# a323-vcf.net
KiCad netlist of a schematic drawn in EAGLE
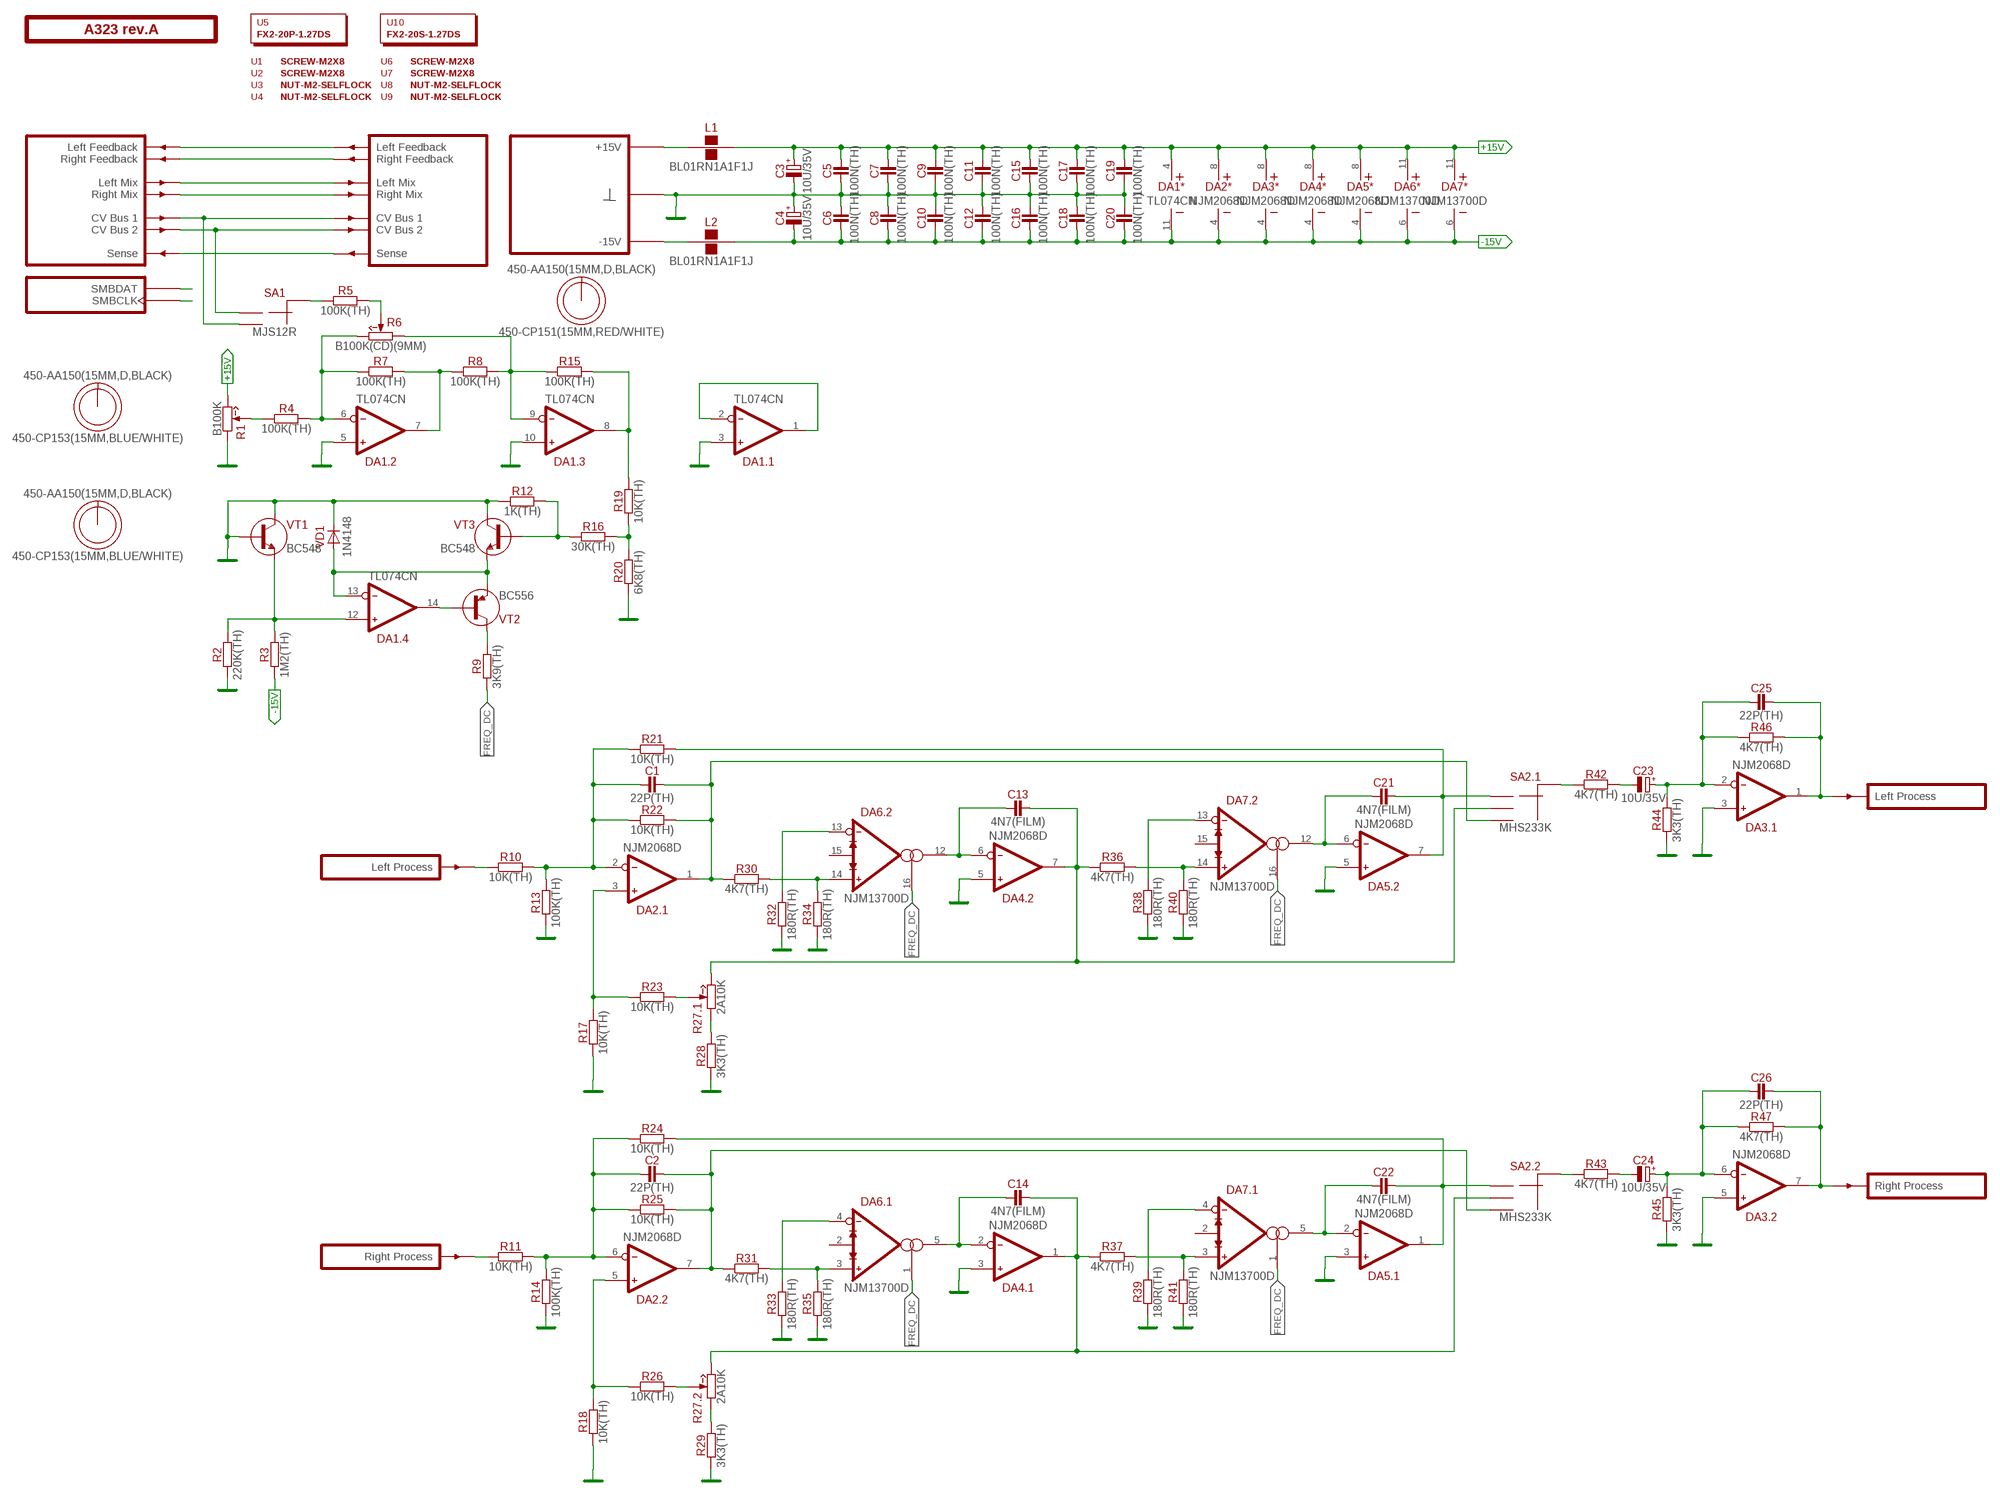
[diagram p0: schematic, sheet 1]

(export (version "E")
  (design (tool "Eeschema 10.0.6"))
  (components
    (comp (ref "C1")
      (value "22P(TH)")
      (footprint "eagle-import:C050-024X044")
      (libsource (lib "eagle-import") (part "?22P(TH)"))
    )
    (comp (ref "C2")
      (value "22P(TH)")
      (footprint "eagle-import:C050-024X044")
      (libsource (lib "eagle-import") (part "?22P(TH)"))
    )
    (comp (ref "C3")
      (value "10U/35V")
      (footprint "eagle-import:E2-5")
      (libsource (lib "eagle-import") (part "?10U/35V"))
    )
    (comp (ref "C4")
      (value "10U/35V")
      (footprint "eagle-import:E2-5")
      (libsource (lib "eagle-import") (part "?10U/35V"))
    )
    (comp (ref "C5")
      (value "100N(TH)")
      (footprint "eagle-import:C050-024X044")
      (libsource (lib "eagle-import") (part "?100N(TH)"))
    )
    (comp (ref "C6")
      (value "100N(TH)")
      (footprint "eagle-import:C050-024X044")
      (libsource (lib "eagle-import") (part "?100N(TH)"))
    )
    (comp (ref "C7")
      (value "100N(TH)")
      (footprint "eagle-import:C050-024X044")
      (libsource (lib "eagle-import") (part "?100N(TH)"))
    )
    (comp (ref "C8")
      (value "100N(TH)")
      (footprint "eagle-import:C050-024X044")
      (libsource (lib "eagle-import") (part "?100N(TH)"))
    )
    (comp (ref "C9")
      (value "100N(TH)")
      (footprint "eagle-import:C050-024X044")
      (libsource (lib "eagle-import") (part "?100N(TH)"))
    )
    (comp (ref "C10")
      (value "100N(TH)")
      (footprint "eagle-import:C050-024X044")
      (libsource (lib "eagle-import") (part "?100N(TH)"))
    )
    (comp (ref "C11")
      (value "100N(TH)")
      (footprint "eagle-import:C050-024X044")
      (libsource (lib "eagle-import") (part "?100N(TH)"))
    )
    (comp (ref "C12")
      (value "100N(TH)")
      (footprint "eagle-import:C050-024X044")
      (libsource (lib "eagle-import") (part "?100N(TH)"))
    )
    (comp (ref "C13")
      (value "4N7(FILM)")
      (footprint "eagle-import:C050-025X075")
      (libsource (lib "eagle-import") (part "?4N7(FILM)"))
    )
    (comp (ref "C14")
      (value "4N7(FILM)")
      (footprint "eagle-import:C050-025X075")
      (libsource (lib "eagle-import") (part "?4N7(FILM)"))
    )
    (comp (ref "C15")
      (value "100N(TH)")
      (footprint "eagle-import:C050-024X044")
      (libsource (lib "eagle-import") (part "?100N(TH)"))
    )
    (comp (ref "C16")
      (value "100N(TH)")
      (footprint "eagle-import:C050-024X044")
      (libsource (lib "eagle-import") (part "?100N(TH)"))
    )
    (comp (ref "C17")
      (value "100N(TH)")
      (footprint "eagle-import:C050-024X044")
      (libsource (lib "eagle-import") (part "?100N(TH)"))
    )
    (comp (ref "C18")
      (value "100N(TH)")
      (footprint "eagle-import:C050-024X044")
      (libsource (lib "eagle-import") (part "?100N(TH)"))
    )
    (comp (ref "C19")
      (value "100N(TH)")
      (footprint "eagle-import:C050-024X044")
      (libsource (lib "eagle-import") (part "?100N(TH)"))
    )
    (comp (ref "C20")
      (value "100N(TH)")
      (footprint "eagle-import:C050-024X044")
      (libsource (lib "eagle-import") (part "?100N(TH)"))
    )
    (comp (ref "C21")
      (value "4N7(FILM)")
      (footprint "eagle-import:C050-025X075")
      (libsource (lib "eagle-import") (part "?4N7(FILM)"))
    )
    (comp (ref "C22")
      (value "4N7(FILM)")
      (footprint "eagle-import:C050-025X075")
      (libsource (lib "eagle-import") (part "?4N7(FILM)"))
    )
    (comp (ref "C23")
      (value "10U/35V")
      (footprint "eagle-import:E2-5")
      (libsource (lib "eagle-import") (part "?10U/35V"))
    )
    (comp (ref "C24")
      (value "10U/35V")
      (footprint "eagle-import:E2-5")
      (libsource (lib "eagle-import") (part "?10U/35V"))
    )
    (comp (ref "C25")
      (value "22P(TH)")
      (footprint "eagle-import:C050-024X044")
      (libsource (lib "eagle-import") (part "?22P(TH)"))
    )
    (comp (ref "C26")
      (value "22P(TH)")
      (footprint "eagle-import:C050-024X044")
      (libsource (lib "eagle-import") (part "?22P(TH)"))
    )
    (comp (ref "DA1")
      (value "TL074CN")
      (footprint "eagle-import:DIP-14")
      (libsource (lib "eagle-import") (part "TL074CN"))
    )
    (comp (ref "DA2")
      (value "NJM2068D")
      (footprint "eagle-import:DIP-8")
      (libsource (lib "eagle-import") (part "NJM2068D"))
    )
    (comp (ref "DA3")
      (value "NJM2068D")
      (footprint "eagle-import:DIP-8")
      (libsource (lib "eagle-import") (part "NJM2068D"))
    )
    (comp (ref "DA4")
      (value "NJM2068D")
      (footprint "eagle-import:DIP-8")
      (libsource (lib "eagle-import") (part "NJM2068D"))
    )
    (comp (ref "DA5")
      (value "NJM2068D")
      (footprint "eagle-import:DIP-8")
      (libsource (lib "eagle-import") (part "NJM2068D"))
    )
    (comp (ref "DA6")
      (value "NJM13700D")
      (footprint "eagle-import:DIP-16")
      (libsource (lib "eagle-import") (part "NJM13700D"))
    )
    (comp (ref "DA7")
      (value "NJM13700D")
      (footprint "eagle-import:DIP-16")
      (libsource (lib "eagle-import") (part "NJM13700D"))
    )
    (comp (ref "L1")
      (value "BL01RN1A1F1J")
      (footprint "eagle-import:BL01RN1A")
      (libsource (lib "eagle-import") (part "BL01RN1A?1F1J"))
    )
    (comp (ref "L2")
      (value "BL01RN1A1F1J")
      (footprint "eagle-import:BL01RN1A")
      (libsource (lib "eagle-import") (part "BL01RN1A?1F1J"))
    )
    (comp (ref "O1")
      (value "450-AA150(15MM,D,BLACK)")
      (footprint "eagle-import:EMPTY")
      (libsource (lib "eagle-import") (part "450-AA?150(15MM,D,BLACK)"))
    )
    (comp (ref "O2")
      (value "450-CP153(15MM,BLUE/WHITE)")
      (footprint "eagle-import:EMPTY")
      (libsource (lib "eagle-import") (part "450-C?P153(15MM,BLUE/WHITE)"))
    )
    (comp (ref "O3")
      (value "450-AA150(15MM,D,BLACK)")
      (footprint "eagle-import:EMPTY")
      (libsource (lib "eagle-import") (part "450-AA?150(15MM,D,BLACK)"))
    )
    (comp (ref "O4")
      (value "450-CP153(15MM,BLUE/WHITE)")
      (footprint "eagle-import:EMPTY")
      (libsource (lib "eagle-import") (part "450-C?P153(15MM,BLUE/WHITE)"))
    )
    (comp (ref "O5")
      (value "450-AA150(15MM,D,BLACK)")
      (footprint "eagle-import:EMPTY")
      (libsource (lib "eagle-import") (part "450-AA?150(15MM,D,BLACK)"))
    )
    (comp (ref "O6")
      (value "450-CP151(15MM,RED/WHITE)")
      (footprint "eagle-import:EMPTY")
      (libsource (lib "eagle-import") (part "450-C?P151(15MM,RED/WHITE)"))
    )
    (comp (ref "PCB1")
      (value "A323 rev.A")
      (footprint "eagle-import:ST2-BOARD-74")
      (libsource (lib "eagle-import") (part "ST2-BOARD-?74"))
    )
    (comp (ref "R1")
      (value "B100K")
      (footprint "eagle-import:RV11-SINGLE")
      (libsource (lib "eagle-import") (part "?B100K"))
    )
    (comp (ref "R2")
      (value "220K(TH)")
      (footprint "eagle-import:R-0207_10")
      (libsource (lib "eagle-import") (part "?220K(TH)"))
    )
    (comp (ref "R3")
      (value "1M2(TH)")
      (footprint "eagle-import:R-0207_10")
      (libsource (lib "eagle-import") (part "?1M2(TH)"))
    )
    (comp (ref "R4")
      (value "100K(TH)")
      (footprint "eagle-import:R-0207_10")
      (libsource (lib "eagle-import") (part "?100K(TH)"))
    )
    (comp (ref "R5")
      (value "100K(TH)")
      (footprint "eagle-import:R-0207_10")
      (libsource (lib "eagle-import") (part "?100K(TH)"))
    )
    (comp (ref "R6")
      (value "B100K(CD)(9MM)")
      (footprint "eagle-import:RV09-SINGLE")
      (libsource (lib "eagle-import") (part "?B100K(CD)(9MM)"))
    )
    (comp (ref "R7")
      (value "100K(TH)")
      (footprint "eagle-import:R-0207_10")
      (libsource (lib "eagle-import") (part "?100K(TH)"))
    )
    (comp (ref "R8")
      (value "100K(TH)")
      (footprint "eagle-import:R-0207_10")
      (libsource (lib "eagle-import") (part "?100K(TH)"))
    )
    (comp (ref "R9")
      (value "3K9(TH)")
      (footprint "eagle-import:R-0207_10")
      (libsource (lib "eagle-import") (part "?3K9(TH)"))
    )
    (comp (ref "R10")
      (value "10K(TH)")
      (footprint "eagle-import:R-0207_10")
      (libsource (lib "eagle-import") (part "?10K(TH)"))
    )
    (comp (ref "R11")
      (value "10K(TH)")
      (footprint "eagle-import:R-0207_10")
      (libsource (lib "eagle-import") (part "?10K(TH)"))
    )
    (comp (ref "R12")
      (value "1K(TH)")
      (footprint "eagle-import:R-0207_10")
      (libsource (lib "eagle-import") (part "?1K(TH)"))
    )
    (comp (ref "R13")
      (value "100K(TH)")
      (footprint "eagle-import:R-0207_10")
      (libsource (lib "eagle-import") (part "?100K(TH)"))
    )
    (comp (ref "R14")
      (value "100K(TH)")
      (footprint "eagle-import:R-0207_10")
      (libsource (lib "eagle-import") (part "?100K(TH)"))
    )
    (comp (ref "R15")
      (value "100K(TH)")
      (footprint "eagle-import:R-0207_10")
      (libsource (lib "eagle-import") (part "?100K(TH)"))
    )
    (comp (ref "R16")
      (value "30K(TH)")
      (footprint "eagle-import:R-0207_10")
      (libsource (lib "eagle-import") (part "?30K(TH)"))
    )
    (comp (ref "R17")
      (value "10K(TH)")
      (footprint "eagle-import:R-0207_10")
      (libsource (lib "eagle-import") (part "?10K(TH)"))
    )
    (comp (ref "R18")
      (value "10K(TH)")
      (footprint "eagle-import:R-0207_10")
      (libsource (lib "eagle-import") (part "?10K(TH)"))
    )
    (comp (ref "R19")
      (value "10K(TH)")
      (footprint "eagle-import:R-0207_10")
      (libsource (lib "eagle-import") (part "?10K(TH)"))
    )
    (comp (ref "R20")
      (value "6K8(TH)")
      (footprint "eagle-import:R-0207_10")
      (libsource (lib "eagle-import") (part "?6K8(TH)"))
    )
    (comp (ref "R21")
      (value "10K(TH)")
      (footprint "eagle-import:R-0207_10")
      (libsource (lib "eagle-import") (part "?10K(TH)"))
    )
    (comp (ref "R22")
      (value "10K(TH)")
      (footprint "eagle-import:R-0207_10")
      (libsource (lib "eagle-import") (part "?10K(TH)"))
    )
    (comp (ref "R23")
      (value "10K(TH)")
      (footprint "eagle-import:R-0207_10")
      (libsource (lib "eagle-import") (part "?10K(TH)"))
    )
    (comp (ref "R24")
      (value "10K(TH)")
      (footprint "eagle-import:R-0207_10")
      (libsource (lib "eagle-import") (part "?10K(TH)"))
    )
    (comp (ref "R25")
      (value "10K(TH)")
      (footprint "eagle-import:R-0207_10")
      (libsource (lib "eagle-import") (part "?10K(TH)"))
    )
    (comp (ref "R26")
      (value "10K(TH)")
      (footprint "eagle-import:R-0207_10")
      (libsource (lib "eagle-import") (part "?10K(TH)"))
    )
    (comp (ref "R27")
      (value "2A10K")
      (footprint "eagle-import:RV11-DUAL")
      (libsource (lib "eagle-import") (part "2?A10K"))
    )
    (comp (ref "R28")
      (value "3K3(TH)")
      (footprint "eagle-import:R-0207_10")
      (libsource (lib "eagle-import") (part "?3K3(TH)"))
    )
    (comp (ref "R29")
      (value "3K3(TH)")
      (footprint "eagle-import:R-0207_10")
      (libsource (lib "eagle-import") (part "?3K3(TH)"))
    )
    (comp (ref "R30")
      (value "4K7(TH)")
      (footprint "eagle-import:R-0207_10")
      (libsource (lib "eagle-import") (part "?4K7(TH)"))
    )
    (comp (ref "R31")
      (value "4K7(TH)")
      (footprint "eagle-import:R-0207_10")
      (libsource (lib "eagle-import") (part "?4K7(TH)"))
    )
    (comp (ref "R32")
      (value "180R(TH)")
      (footprint "eagle-import:R-0207_10")
      (libsource (lib "eagle-import") (part "?180R(TH)"))
    )
    (comp (ref "R33")
      (value "180R(TH)")
      (footprint "eagle-import:R-0207_10")
      (libsource (lib "eagle-import") (part "?180R(TH)"))
    )
    (comp (ref "R34")
      (value "180R(TH)")
      (footprint "eagle-import:R-0207_10")
      (libsource (lib "eagle-import") (part "?180R(TH)"))
    )
    (comp (ref "R35")
      (value "180R(TH)")
      (footprint "eagle-import:R-0207_10")
      (libsource (lib "eagle-import") (part "?180R(TH)"))
    )
    (comp (ref "R36")
      (value "4K7(TH)")
      (footprint "eagle-import:R-0207_10")
      (libsource (lib "eagle-import") (part "?4K7(TH)"))
    )
    (comp (ref "R37")
      (value "4K7(TH)")
      (footprint "eagle-import:R-0207_10")
      (libsource (lib "eagle-import") (part "?4K7(TH)"))
    )
    (comp (ref "R38")
      (value "180R(TH)")
      (footprint "eagle-import:R-0207_10")
      (libsource (lib "eagle-import") (part "?180R(TH)"))
    )
    (comp (ref "R39")
      (value "180R(TH)")
      (footprint "eagle-import:R-0207_10")
      (libsource (lib "eagle-import") (part "?180R(TH)"))
    )
    (comp (ref "R40")
      (value "180R(TH)")
      (footprint "eagle-import:R-0207_10")
      (libsource (lib "eagle-import") (part "?180R(TH)"))
    )
    (comp (ref "R41")
      (value "180R(TH)")
      (footprint "eagle-import:R-0207_10")
      (libsource (lib "eagle-import") (part "?180R(TH)"))
    )
    (comp (ref "R42")
      (value "4K7(TH)")
      (footprint "eagle-import:R-0207_10")
      (libsource (lib "eagle-import") (part "?4K7(TH)"))
    )
    (comp (ref "R43")
      (value "4K7(TH)")
      (footprint "eagle-import:R-0207_10")
      (libsource (lib "eagle-import") (part "?4K7(TH)"))
    )
    (comp (ref "R44")
      (value "3K3(TH)")
      (footprint "eagle-import:R-0207_10")
      (libsource (lib "eagle-import") (part "?3K3(TH)"))
    )
    (comp (ref "R45")
      (value "3K3(TH)")
      (footprint "eagle-import:R-0207_10")
      (libsource (lib "eagle-import") (part "?3K3(TH)"))
    )
    (comp (ref "R46")
      (value "4K7(TH)")
      (footprint "eagle-import:R-0207_10")
      (libsource (lib "eagle-import") (part "?4K7(TH)"))
    )
    (comp (ref "R47")
      (value "4K7(TH)")
      (footprint "eagle-import:R-0207_10")
      (libsource (lib "eagle-import") (part "?4K7(TH)"))
    )
    (comp (ref "SA1")
      (value "MJS12R")
      (footprint "eagle-import:APEM-MJS12R")
      (libsource (lib "eagle-import") (part "MJS12R"))
    )
    (comp (ref "SA2")
      (value "MHS233K")
      (footprint "eagle-import:APEM-MHS233K")
      (libsource (lib "eagle-import") (part "MHS233K"))
    )
    (comp (ref "U1")
      (value "SCREW-M2X8")
      (footprint "eagle-import:EMPTY")
      (libsource (lib "eagle-import") (part "?SCREW-M2X8"))
    )
    (comp (ref "U2")
      (value "SCREW-M2X8")
      (footprint "eagle-import:EMPTY")
      (libsource (lib "eagle-import") (part "?SCREW-M2X8"))
    )
    (comp (ref "U3")
      (value "NUT-M2-SELFLOCK")
      (footprint "eagle-import:EMPTY")
      (libsource (lib "eagle-import") (part "?NUT-M2-SELFLOCK"))
    )
    (comp (ref "U4")
      (value "NUT-M2-SELFLOCK")
      (footprint "eagle-import:EMPTY")
      (libsource (lib "eagle-import") (part "?NUT-M2-SELFLOCK"))
    )
    (comp (ref "U5")
      (value "FX2-20P-1.27DS")
      (footprint "eagle-import:EMPTY")
      (libsource (lib "eagle-import") (part "?FX2-20P-1.27DS"))
    )
    (comp (ref "U6")
      (value "SCREW-M2X8")
      (footprint "eagle-import:EMPTY")
      (libsource (lib "eagle-import") (part "?SCREW-M2X8"))
    )
    (comp (ref "U7")
      (value "SCREW-M2X8")
      (footprint "eagle-import:EMPTY")
      (libsource (lib "eagle-import") (part "?SCREW-M2X8"))
    )
    (comp (ref "U8")
      (value "NUT-M2-SELFLOCK")
      (footprint "eagle-import:EMPTY")
      (libsource (lib "eagle-import") (part "?NUT-M2-SELFLOCK"))
    )
    (comp (ref "U9")
      (value "NUT-M2-SELFLOCK")
      (footprint "eagle-import:EMPTY")
      (libsource (lib "eagle-import") (part "?NUT-M2-SELFLOCK"))
    )
    (comp (ref "U10")
      (value "FX2-20S-1.27DS")
      (footprint "eagle-import:EMPTY")
      (libsource (lib "eagle-import") (part "?FX2-20S-1.27DS"))
    )
    (comp (ref "VD1")
      (value "1N4148")
      (footprint "eagle-import:DO35-7")
      (libsource (lib "eagle-import") (part "?1N4148"))
    )
    (comp (ref "VT1")
      (value "BC548")
      (footprint "eagle-import:TO92")
      (libsource (lib "eagle-import") (part "?BC548"))
    )
    (comp (ref "VT2")
      (value "BC556")
      (footprint "eagle-import:TO92")
      (libsource (lib "eagle-import") (part "?BC556"))
    )
    (comp (ref "VT3")
      (value "BC548")
      (footprint "eagle-import:TO92")
      (libsource (lib "eagle-import") (part "?BC548"))
    )
  )
  (nets
    (net (code "1") (name "+15V") (class "Default")
      (node (ref "C11") (pin "2") (pinfunction "2_2") (pintype "passive"))
      (node (ref "C15") (pin "2") (pinfunction "2_2") (pintype "passive"))
      (node (ref "C17") (pin "2") (pinfunction "2_2") (pintype "passive"))
      (node (ref "C19") (pin "2") (pinfunction "2_2") (pintype "passive"))
      (node (ref "C3") (pin "+") (pinfunction "+_+") (pintype "passive"))
      (node (ref "C5") (pin "2") (pinfunction "2_2") (pintype "passive"))
      (node (ref "C7") (pin "2") (pinfunction "2_2") (pintype "passive"))
      (node (ref "C9") (pin "2") (pinfunction "2_2") (pintype "passive"))
      (node (ref "DA1") (pin "4") (pinfunction "V+_4") (pintype "power_in"))
      (node (ref "DA2") (pin "8") (pinfunction "V+_8") (pintype "power_in"))
      (node (ref "DA3") (pin "8") (pinfunction "V+_8") (pintype "power_in"))
      (node (ref "DA4") (pin "8") (pinfunction "V+_8") (pintype "power_in"))
      (node (ref "DA5") (pin "8") (pinfunction "V+_8") (pintype "power_in"))
      (node (ref "DA6") (pin "11") (pinfunction "V+_11") (pintype "power_in"))
      (node (ref "DA7") (pin "11") (pinfunction "V+_11") (pintype "power_in"))
      (node (ref "L1") (pin "2") (pinfunction "2_2") (pintype "passive"))
      (node (ref "R1") (pin "3") (pinfunction "CW_3") (pintype "passive"))
    )
    (net (code "2") (name "-15V") (class "Default")
      (node (ref "C10") (pin "1") (pinfunction "1_1") (pintype "passive"))
      (node (ref "C12") (pin "1") (pinfunction "1_1") (pintype "passive"))
      (node (ref "C16") (pin "1") (pinfunction "1_1") (pintype "passive"))
      (node (ref "C18") (pin "1") (pinfunction "1_1") (pintype "passive"))
      (node (ref "C20") (pin "1") (pinfunction "1_1") (pintype "passive"))
      (node (ref "C4") (pin "-") (pinfunction "-_-") (pintype "passive"))
      (node (ref "C6") (pin "1") (pinfunction "1_1") (pintype "passive"))
      (node (ref "C8") (pin "1") (pinfunction "1_1") (pintype "passive"))
      (node (ref "DA1") (pin "11") (pinfunction "V-_11") (pintype "power_in"))
      (node (ref "DA2") (pin "4") (pinfunction "V-_4") (pintype "power_in"))
      (node (ref "DA3") (pin "4") (pinfunction "V-_4") (pintype "power_in"))
      (node (ref "DA4") (pin "4") (pinfunction "V-_4") (pintype "power_in"))
      (node (ref "DA5") (pin "4") (pinfunction "V-_4") (pintype "power_in"))
      (node (ref "DA6") (pin "6") (pinfunction "V-_6") (pintype "power_in"))
      (node (ref "DA7") (pin "6") (pinfunction "V-_6") (pintype "power_in"))
      (node (ref "L2") (pin "2") (pinfunction "2_2") (pintype "passive"))
      (node (ref "R3") (pin "1") (pinfunction "1_1") (pintype "passive"))
    )
    (net (code "3") (name "FREQ_DC") (class "Default")
      (node (ref "DA6") (pin "1") (pinfunction "AMP_BIAS_1") (pintype "input"))
      (node (ref "DA6") (pin "16") (pinfunction "AMP_BIAS_16") (pintype "input"))
      (node (ref "DA7") (pin "1") (pinfunction "AMP_BIAS_1") (pintype "input"))
      (node (ref "DA7") (pin "16") (pinfunction "AMP_BIAS_16") (pintype "input"))
      (node (ref "R9") (pin "1") (pinfunction "1_1") (pintype "passive"))
    )
    (net (code "4") (name "GND") (class "Default")
      (node (ref "C10") (pin "2") (pinfunction "2_2") (pintype "passive"))
      (node (ref "C11") (pin "1") (pinfunction "1_1") (pintype "passive"))
      (node (ref "C12") (pin "2") (pinfunction "2_2") (pintype "passive"))
      (node (ref "C15") (pin "1") (pinfunction "1_1") (pintype "passive"))
      (node (ref "C16") (pin "2") (pinfunction "2_2") (pintype "passive"))
      (node (ref "C17") (pin "1") (pinfunction "1_1") (pintype "passive"))
      (node (ref "C18") (pin "2") (pinfunction "2_2") (pintype "passive"))
      (node (ref "C19") (pin "1") (pinfunction "1_1") (pintype "passive"))
      (node (ref "C20") (pin "2") (pinfunction "2_2") (pintype "passive"))
      (node (ref "C3") (pin "-") (pinfunction "-_-") (pintype "passive"))
      (node (ref "C4") (pin "+") (pinfunction "+_+") (pintype "passive"))
      (node (ref "C5") (pin "1") (pinfunction "1_1") (pintype "passive"))
      (node (ref "C6") (pin "2") (pinfunction "2_2") (pintype "passive"))
      (node (ref "C7") (pin "1") (pinfunction "1_1") (pintype "passive"))
      (node (ref "C8") (pin "2") (pinfunction "2_2") (pintype "passive"))
      (node (ref "C9") (pin "1") (pinfunction "1_1") (pintype "passive"))
      (node (ref "DA1") (pin "10") (pinfunction "IN+_10") (pintype "input"))
      (node (ref "DA1") (pin "3") (pinfunction "IN+_3") (pintype "input"))
      (node (ref "DA1") (pin "5") (pinfunction "IN+_5") (pintype "input"))
      (node (ref "DA3") (pin "3") (pinfunction "IN+_3") (pintype "input"))
      (node (ref "DA3") (pin "5") (pinfunction "IN+_5") (pintype "input"))
      (node (ref "DA4") (pin "3") (pinfunction "IN+_3") (pintype "input"))
      (node (ref "DA4") (pin "5") (pinfunction "IN+_5") (pintype "input"))
      (node (ref "DA5") (pin "3") (pinfunction "IN+_3") (pintype "input"))
      (node (ref "DA5") (pin "5") (pinfunction "IN+_5") (pintype "input"))
      (node (ref "PCB1") (pin "B4") (pinfunction "GND_B4") (pintype "bidirectional"))
      (node (ref "PCB1") (pin "B4'") (pinfunction "GND_B4'") (pintype "bidirectional"))
      (node (ref "PCB1") (pin "B5") (pinfunction "GND_B5") (pintype "bidirectional"))
      (node (ref "PCB1") (pin "B5'") (pinfunction "GND_B5'") (pintype "bidirectional"))
      (node (ref "PCB1") (pin "B6") (pinfunction "GND_B6") (pintype "bidirectional"))
      (node (ref "PCB1") (pin "B6'") (pinfunction "GND_B6'") (pintype "bidirectional"))
      (node (ref "PCB1") (pin "B7") (pinfunction "GND_B7") (pintype "bidirectional"))
      (node (ref "PCB1") (pin "B7'") (pinfunction "GND_B7'") (pintype "bidirectional"))
      (node (ref "PCB1") (pin "B8") (pinfunction "GND_B8") (pintype "bidirectional"))
      (node (ref "PCB1") (pin "B8'") (pinfunction "GND_B8'") (pintype "bidirectional"))
      (node (ref "R1") (pin "1") (pinfunction "CCW_1") (pintype "passive"))
      (node (ref "R12") (pin "1") (pinfunction "1_1") (pintype "passive"))
      (node (ref "R13") (pin "1") (pinfunction "1_1") (pintype "passive"))
      (node (ref "R14") (pin "1") (pinfunction "1_1") (pintype "passive"))
      (node (ref "R17") (pin "1") (pinfunction "1_1") (pintype "passive"))
      (node (ref "R18") (pin "1") (pinfunction "1_1") (pintype "passive"))
      (node (ref "R2") (pin "1") (pinfunction "1_1") (pintype "passive"))
      (node (ref "R20") (pin "1") (pinfunction "1_1") (pintype "passive"))
      (node (ref "R28") (pin "1") (pinfunction "1_1") (pintype "passive"))
      (node (ref "R29") (pin "1") (pinfunction "1_1") (pintype "passive"))
      (node (ref "R32") (pin "1") (pinfunction "1_1") (pintype "passive"))
      (node (ref "R33") (pin "1") (pinfunction "1_1") (pintype "passive"))
      (node (ref "R34") (pin "1") (pinfunction "1_1") (pintype "passive"))
      (node (ref "R35") (pin "1") (pinfunction "1_1") (pintype "passive"))
      (node (ref "R38") (pin "1") (pinfunction "1_1") (pintype "passive"))
      (node (ref "R39") (pin "1") (pinfunction "1_1") (pintype "passive"))
      (node (ref "R40") (pin "1") (pinfunction "1_1") (pintype "passive"))
      (node (ref "R41") (pin "1") (pinfunction "1_1") (pintype "passive"))
      (node (ref "R44") (pin "1") (pinfunction "1_1") (pintype "passive"))
      (node (ref "R45") (pin "1") (pinfunction "1_1") (pintype "passive"))
      (node (ref "VD1") (pin "C") (pinfunction "C_C") (pintype "passive"))
      (node (ref "VT1") (pin "1") (pinfunction "C_1") (pintype "passive"))
      (node (ref "VT1") (pin "2") (pinfunction "B_2") (pintype "passive"))
      (node (ref "VT3") (pin "1") (pinfunction "C_1") (pintype "passive"))
    )
    (net (code "5") (name "Net-(C23-Pad-)") (class "Default")
      (node (ref "C23") (pin "-") (pinfunction "-_-") (pintype "passive"))
      (node (ref "R42") (pin "2") (pinfunction "2_2") (pintype "passive"))
    )
    (net (code "6") (name "Net-(C24-Pad-)") (class "Default")
      (node (ref "C24") (pin "-") (pinfunction "-_-") (pintype "passive"))
      (node (ref "R43") (pin "2") (pinfunction "2_2") (pintype "passive"))
    )
    (net (code "7") (name "Net-(DA1B-IN-)") (class "Default")
      (node (ref "DA1") (pin "1") (pinfunction "OUT_1") (pintype "output"))
      (node (ref "DA1") (pin "2") (pinfunction "IN-_2") (pintype "input"))
    )
    (net (code "8") (name "Net-(DA1C-IN-)") (class "Default")
      (node (ref "DA1") (pin "6") (pinfunction "IN-_6") (pintype "input"))
      (node (ref "R4") (pin "2") (pinfunction "2_2") (pintype "passive"))
      (node (ref "R6") (pin "3") (pinfunction "CW_3") (pintype "passive"))
      (node (ref "R7") (pin "1") (pinfunction "1_1") (pintype "passive"))
    )
    (net (code "9") (name "Net-(DA1C-OUT)") (class "Default")
      (node (ref "DA1") (pin "7") (pinfunction "OUT_7") (pintype "output"))
      (node (ref "R7") (pin "2") (pinfunction "2_2") (pintype "passive"))
      (node (ref "R8") (pin "1") (pinfunction "1_1") (pintype "passive"))
    )
    (net (code "10") (name "Net-(DA1D-IN-)") (class "Default")
      (node (ref "DA1") (pin "9") (pinfunction "IN-_9") (pintype "input"))
      (node (ref "R15") (pin "1") (pinfunction "1_1") (pintype "passive"))
      (node (ref "R6") (pin "1") (pinfunction "CCW_1") (pintype "passive"))
      (node (ref "R8") (pin "2") (pinfunction "2_2") (pintype "passive"))
    )
    (net (code "11") (name "Net-(DA1D-OUT)") (class "Default")
      (node (ref "DA1") (pin "8") (pinfunction "OUT_8") (pintype "output"))
      (node (ref "R15") (pin "2") (pinfunction "2_2") (pintype "passive"))
      (node (ref "R19") (pin "2") (pinfunction "2_2") (pintype "passive"))
    )
    (net (code "12") (name "Net-(DA1E-IN+)") (class "Default")
      (node (ref "DA1") (pin "12") (pinfunction "IN+_12") (pintype "input"))
      (node (ref "R2") (pin "2") (pinfunction "2_2") (pintype "passive"))
      (node (ref "R3") (pin "2") (pinfunction "2_2") (pintype "passive"))
      (node (ref "VT1") (pin "3") (pinfunction "E_3") (pintype "passive"))
    )
    (net (code "13") (name "Net-(DA1E-IN-)") (class "Default")
      (node (ref "DA1") (pin "13") (pinfunction "IN-_13") (pintype "input"))
      (node (ref "VD1") (pin "A") (pinfunction "A_A") (pintype "passive"))
      (node (ref "VT2") (pin "3") (pinfunction "E_3") (pintype "passive"))
      (node (ref "VT3") (pin "3") (pinfunction "E_3") (pintype "passive"))
    )
    (net (code "14") (name "Net-(DA1E-OUT)") (class "Default")
      (node (ref "DA1") (pin "14") (pinfunction "OUT_14") (pintype "output"))
      (node (ref "VT2") (pin "2") (pinfunction "B_2") (pintype "passive"))
    )
    (net (code "15") (name "Net-(DA2B-IN+)") (class "Default")
      (node (ref "DA2") (pin "3") (pinfunction "IN+_3") (pintype "input"))
      (node (ref "R17") (pin "2") (pinfunction "2_2") (pintype "passive"))
      (node (ref "R23") (pin "1") (pinfunction "1_1") (pintype "passive"))
    )
    (net (code "16") (name "Net-(DA2B-IN-)") (class "Default")
      (node (ref "C1") (pin "1") (pinfunction "1_1") (pintype "passive"))
      (node (ref "DA2") (pin "2") (pinfunction "IN-_2") (pintype "input"))
      (node (ref "R10") (pin "2") (pinfunction "2_2") (pintype "passive"))
      (node (ref "R13") (pin "2") (pinfunction "2_2") (pintype "passive"))
      (node (ref "R21") (pin "1") (pinfunction "1_1") (pintype "passive"))
      (node (ref "R22") (pin "1") (pinfunction "1_1") (pintype "passive"))
    )
    (net (code "17") (name "Net-(DA2B-OUT)") (class "Default")
      (node (ref "C1") (pin "2") (pinfunction "2_2") (pintype "passive"))
      (node (ref "DA2") (pin "1") (pinfunction "OUT_1") (pintype "output"))
      (node (ref "R22") (pin "2") (pinfunction "2_2") (pintype "passive"))
      (node (ref "R30") (pin "1") (pinfunction "1_1") (pintype "passive"))
      (node (ref "SA2") (pin "3") (pinfunction "3_3") (pintype "passive"))
    )
    (net (code "18") (name "Net-(DA2C-IN+)") (class "Default")
      (node (ref "DA2") (pin "5") (pinfunction "IN+_5") (pintype "input"))
      (node (ref "R18") (pin "2") (pinfunction "2_2") (pintype "passive"))
      (node (ref "R26") (pin "1") (pinfunction "1_1") (pintype "passive"))
    )
    (net (code "19") (name "Net-(DA2C-IN-)") (class "Default")
      (node (ref "C2") (pin "1") (pinfunction "1_1") (pintype "passive"))
      (node (ref "DA2") (pin "6") (pinfunction "IN-_6") (pintype "input"))
      (node (ref "R11") (pin "2") (pinfunction "2_2") (pintype "passive"))
      (node (ref "R14") (pin "2") (pinfunction "2_2") (pintype "passive"))
      (node (ref "R24") (pin "1") (pinfunction "1_1") (pintype "passive"))
      (node (ref "R25") (pin "1") (pinfunction "1_1") (pintype "passive"))
    )
    (net (code "20") (name "Net-(DA2C-OUT)") (class "Default")
      (node (ref "C2") (pin "2") (pinfunction "2_2") (pintype "passive"))
      (node (ref "DA2") (pin "7") (pinfunction "OUT_7") (pintype "output"))
      (node (ref "R25") (pin "2") (pinfunction "2_2") (pintype "passive"))
      (node (ref "R31") (pin "1") (pinfunction "1_1") (pintype "passive"))
      (node (ref "SA2") (pin "3'") (pinfunction "3_3'") (pintype "passive"))
    )
    (net (code "21") (name "Net-(DA3B-IN-)") (class "Default")
      (node (ref "C23") (pin "+") (pinfunction "+_+") (pintype "passive"))
      (node (ref "C25") (pin "1") (pinfunction "1_1") (pintype "passive"))
      (node (ref "DA3") (pin "2") (pinfunction "IN-_2") (pintype "input"))
      (node (ref "R44") (pin "2") (pinfunction "2_2") (pintype "passive"))
      (node (ref "R46") (pin "1") (pinfunction "1_1") (pintype "passive"))
    )
    (net (code "22") (name "Net-(DA3B-OUT)") (class "Default")
      (node (ref "C25") (pin "2") (pinfunction "2_2") (pintype "passive"))
      (node (ref "DA3") (pin "1") (pinfunction "OUT_1") (pintype "output"))
      (node (ref "PCB1") (pin "BOUTL'") (pinfunction "OUTL_BOUTL'") (pintype "bidirectional"))
      (node (ref "R46") (pin "2") (pinfunction "2_2") (pintype "passive"))
    )
    (net (code "23") (name "Net-(DA3C-IN-)") (class "Default")
      (node (ref "C24") (pin "+") (pinfunction "+_+") (pintype "passive"))
      (node (ref "C26") (pin "1") (pinfunction "1_1") (pintype "passive"))
      (node (ref "DA3") (pin "6") (pinfunction "IN-_6") (pintype "input"))
      (node (ref "R45") (pin "2") (pinfunction "2_2") (pintype "passive"))
      (node (ref "R47") (pin "1") (pinfunction "1_1") (pintype "passive"))
    )
    (net (code "24") (name "Net-(DA3C-OUT)") (class "Default")
      (node (ref "C26") (pin "2") (pinfunction "2_2") (pintype "passive"))
      (node (ref "DA3") (pin "7") (pinfunction "OUT_7") (pintype "output"))
      (node (ref "PCB1") (pin "BOUTR'") (pinfunction "OUTR_BOUTR'") (pintype "bidirectional"))
      (node (ref "R47") (pin "2") (pinfunction "2_2") (pintype "passive"))
    )
    (net (code "25") (name "Net-(DA4B-IN-)") (class "Default")
      (node (ref "C14") (pin "1") (pinfunction "1_1") (pintype "passive"))
      (node (ref "DA4") (pin "2") (pinfunction "IN-_2") (pintype "input"))
      (node (ref "DA6") (pin "5") (pinfunction "OUT_5") (pintype "output"))
    )
    (net (code "26") (name "Net-(DA4B-OUT)") (class "Default")
      (node (ref "C14") (pin "2") (pinfunction "2_2") (pintype "passive"))
      (node (ref "DA4") (pin "1") (pinfunction "OUT_1") (pintype "output"))
      (node (ref "R27") (pin "3'") (pinfunction "CW_3'") (pintype "passive"))
      (node (ref "R37") (pin "1") (pinfunction "1_1") (pintype "passive"))
      (node (ref "SA2") (pin "2'") (pinfunction "2_2'") (pintype "passive"))
    )
    (net (code "27") (name "Net-(DA4C-IN-)") (class "Default")
      (node (ref "C13") (pin "1") (pinfunction "1_1") (pintype "passive"))
      (node (ref "DA4") (pin "6") (pinfunction "IN-_6") (pintype "input"))
      (node (ref "DA6") (pin "12") (pinfunction "OUT_12") (pintype "output"))
    )
    (net (code "28") (name "Net-(DA4C-OUT)") (class "Default")
      (node (ref "C13") (pin "2") (pinfunction "2_2") (pintype "passive"))
      (node (ref "DA4") (pin "7") (pinfunction "OUT_7") (pintype "output"))
      (node (ref "R27") (pin "3") (pinfunction "CW_3") (pintype "passive"))
      (node (ref "R36") (pin "1") (pinfunction "1_1") (pintype "passive"))
      (node (ref "SA2") (pin "2") (pinfunction "2_2") (pintype "passive"))
    )
    (net (code "29") (name "Net-(DA5B-IN-)") (class "Default")
      (node (ref "C22") (pin "1") (pinfunction "1_1") (pintype "passive"))
      (node (ref "DA5") (pin "2") (pinfunction "IN-_2") (pintype "input"))
      (node (ref "DA7") (pin "5") (pinfunction "OUT_5") (pintype "output"))
    )
    (net (code "30") (name "Net-(DA5B-OUT)") (class "Default")
      (node (ref "C22") (pin "2") (pinfunction "2_2") (pintype "passive"))
      (node (ref "DA5") (pin "1") (pinfunction "OUT_1") (pintype "output"))
      (node (ref "R24") (pin "2") (pinfunction "2_2") (pintype "passive"))
      (node (ref "SA2") (pin "1'") (pinfunction "1_1'") (pintype "passive"))
    )
    (net (code "31") (name "Net-(DA5C-IN-)") (class "Default")
      (node (ref "C21") (pin "1") (pinfunction "1_1") (pintype "passive"))
      (node (ref "DA5") (pin "6") (pinfunction "IN-_6") (pintype "input"))
      (node (ref "DA7") (pin "12") (pinfunction "OUT_12") (pintype "output"))
    )
    (net (code "32") (name "Net-(DA5C-OUT)") (class "Default")
      (node (ref "C21") (pin "2") (pinfunction "2_2") (pintype "passive"))
      (node (ref "DA5") (pin "7") (pinfunction "OUT_7") (pintype "output"))
      (node (ref "R21") (pin "2") (pinfunction "2_2") (pintype "passive"))
      (node (ref "SA2") (pin "1") (pinfunction "1_1") (pintype "passive"))
    )
    (net (code "33") (name "Net-(DA6B-IN+)") (class "Default")
      (node (ref "DA6") (pin "3") (pinfunction "IN+_3") (pintype "input"))
      (node (ref "R31") (pin "2") (pinfunction "2_2") (pintype "passive"))
      (node (ref "R35") (pin "2") (pinfunction "2_2") (pintype "passive"))
    )
    (net (code "34") (name "Net-(DA6B-IN-)") (class "Default")
      (node (ref "DA6") (pin "4") (pinfunction "IN-_4") (pintype "input"))
      (node (ref "R33") (pin "2") (pinfunction "2_2") (pintype "passive"))
    )
    (net (code "35") (name "Net-(DA6C-IN+)") (class "Default")
      (node (ref "DA6") (pin "14") (pinfunction "IN+_14") (pintype "input"))
      (node (ref "R30") (pin "2") (pinfunction "2_2") (pintype "passive"))
      (node (ref "R34") (pin "2") (pinfunction "2_2") (pintype "passive"))
    )
    (net (code "36") (name "Net-(DA6C-IN-)") (class "Default")
      (node (ref "DA6") (pin "13") (pinfunction "IN-_13") (pintype "input"))
      (node (ref "R32") (pin "2") (pinfunction "2_2") (pintype "passive"))
    )
    (net (code "37") (name "Net-(DA7B-IN+)") (class "Default")
      (node (ref "DA7") (pin "3") (pinfunction "IN+_3") (pintype "input"))
      (node (ref "R37") (pin "2") (pinfunction "2_2") (pintype "passive"))
      (node (ref "R41") (pin "2") (pinfunction "2_2") (pintype "passive"))
    )
    (net (code "38") (name "Net-(DA7B-IN-)") (class "Default")
      (node (ref "DA7") (pin "4") (pinfunction "IN-_4") (pintype "input"))
      (node (ref "R39") (pin "2") (pinfunction "2_2") (pintype "passive"))
    )
    (net (code "39") (name "Net-(DA7C-IN+)") (class "Default")
      (node (ref "DA7") (pin "14") (pinfunction "IN+_14") (pintype "input"))
      (node (ref "R36") (pin "2") (pinfunction "2_2") (pintype "passive"))
      (node (ref "R40") (pin "2") (pinfunction "2_2") (pintype "passive"))
    )
    (net (code "40") (name "Net-(DA7C-IN-)") (class "Default")
      (node (ref "DA7") (pin "13") (pinfunction "IN-_13") (pintype "input"))
      (node (ref "R38") (pin "2") (pinfunction "2_2") (pintype "passive"))
    )
    (net (code "41") (name "Net-(L1-Pad1)") (class "Default")
      (node (ref "L1") (pin "1") (pinfunction "1_1") (pintype "passive"))
      (node (ref "PCB1") (pin "A+15") (pinfunction "P+15V_A+15") (pintype "bidirectional"))
      (node (ref "PCB1") (pin "A+15'") (pinfunction "P+15V_A+15'") (pintype "bidirectional"))
      (node (ref "PCB1") (pin "B+15") (pinfunction "P+15V_B+15") (pintype "bidirectional"))
      (node (ref "PCB1") (pin "B+15'") (pinfunction "P+15V_B+15'") (pintype "bidirectional"))
    )
    (net (code "42") (name "Net-(L2-Pad1)") (class "Default")
      (node (ref "L2") (pin "1") (pinfunction "1_1") (pintype "passive"))
      (node (ref "PCB1") (pin "A-15") (pinfunction "P-15V_A-15") (pintype "bidirectional"))
      (node (ref "PCB1") (pin "A-15'") (pinfunction "P-15V_A-15'") (pintype "bidirectional"))
      (node (ref "PCB1") (pin "B-15") (pinfunction "P-15V_B-15") (pintype "bidirectional"))
      (node (ref "PCB1") (pin "B-15'") (pinfunction "P-15V_B-15'") (pintype "bidirectional"))
    )
    (net (code "43") (name "Net-(PCB1B-INL)") (class "Default")
      (node (ref "PCB1") (pin "BINL") (pinfunction "INL_BINL") (pintype "bidirectional"))
      (node (ref "R10") (pin "1") (pinfunction "1_1") (pintype "passive"))
    )
    (net (code "44") (name "Net-(PCB1C-INR)") (class "Default")
      (node (ref "PCB1") (pin "BINR") (pinfunction "INR_BINR") (pintype "bidirectional"))
      (node (ref "R11") (pin "1") (pinfunction "1_1") (pintype "passive"))
    )
    (net (code "45") (name "Net-(PCB1F-CV1)") (class "Default")
      (node (ref "PCB1") (pin "ACV1") (pinfunction "CV1_ACV1") (pintype "bidirectional"))
      (node (ref "PCB1") (pin "ACV1'") (pinfunction "CV1'_ACV1'") (pintype "bidirectional"))
      (node (ref "SA1") (pin "NO") (pinfunction "2_NO") (pintype "passive"))
    )
    (net (code "46") (name "Net-(PCB1F-CV2)") (class "Default")
      (node (ref "PCB1") (pin "ACV2") (pinfunction "CV2_ACV2") (pintype "bidirectional"))
      (node (ref "PCB1") (pin "ACV2'") (pinfunction "CV2'_ACV2'") (pintype "bidirectional"))
      (node (ref "SA1") (pin "NC") (pinfunction "1_NC") (pintype "passive"))
    )
    (net (code "47") (name "Net-(PCB1F-LFBK)") (class "Default")
      (node (ref "PCB1") (pin "ALFBK") (pinfunction "LFBK_ALFBK") (pintype "bidirectional"))
      (node (ref "PCB1") (pin "ALFBK'") (pinfunction "LFBK'_ALFBK'") (pintype "bidirectional"))
    )
    (net (code "48") (name "Net-(PCB1F-LMIX)") (class "Default")
      (node (ref "PCB1") (pin "ALMIX") (pinfunction "LMIX_ALMIX") (pintype "bidirectional"))
      (node (ref "PCB1") (pin "ALMIX'") (pinfunction "LMIX'_ALMIX'") (pintype "bidirectional"))
    )
    (net (code "49") (name "Net-(PCB1F-RFBK)") (class "Default")
      (node (ref "PCB1") (pin "ARFBK") (pinfunction "RFBK_ARFBK") (pintype "bidirectional"))
      (node (ref "PCB1") (pin "ARFBK'") (pinfunction "RFBK'_ARFBK'") (pintype "bidirectional"))
    )
    (net (code "50") (name "Net-(PCB1F-RMIX)") (class "Default")
      (node (ref "PCB1") (pin "ARMIX") (pinfunction "RMIX_ARMIX") (pintype "bidirectional"))
      (node (ref "PCB1") (pin "ARMIX'") (pinfunction "RMIX'_ARMIX'") (pintype "bidirectional"))
    )
    (net (code "51") (name "Net-(PCB1F-SENSE)") (class "Default")
      (node (ref "PCB1") (pin "BSENSE") (pinfunction "SENSE_BSENSE") (pintype "bidirectional"))
      (node (ref "PCB1") (pin "BSENSE'") (pinfunction "SENSE'_BSENSE'") (pintype "bidirectional"))
    )
    (net (code "52") (name "Net-(PCB1H-SMBCLK-PadASMBCLK')") (class "Default")
      (node (ref "PCB1") (pin "ASMBCLK") (pinfunction "SMBCLK_ASMBCLK") (pintype "bidirectional"))
      (node (ref "PCB1") (pin "ASMBCLK'") (pinfunction "SMBCLK_ASMBCLK'") (pintype "bidirectional"))
    )
    (net (code "53") (name "Net-(PCB1H-SMBDAT-PadASMBDAT')") (class "Default")
      (node (ref "PCB1") (pin "ASMBDAT") (pinfunction "SMBDAT_ASMBDAT") (pintype "bidirectional"))
      (node (ref "PCB1") (pin "ASMBDAT'") (pinfunction "SMBDAT_ASMBDAT'") (pintype "bidirectional"))
    )
    (net (code "54") (name "Net-(R1-W)") (class "Default")
      (node (ref "R1") (pin "2") (pinfunction "W_2") (pintype "passive"))
      (node (ref "R4") (pin "1") (pinfunction "1_1") (pintype "passive"))
    )
    (net (code "55") (name "Net-(R6-W)") (class "Default")
      (node (ref "R5") (pin "2") (pinfunction "2_2") (pintype "passive"))
      (node (ref "R6") (pin "2") (pinfunction "W_2") (pintype "passive"))
    )
    (net (code "56") (name "Net-(R16-Pad2)") (class "Default")
      (node (ref "R16") (pin "2") (pinfunction "2_2") (pintype "passive"))
      (node (ref "R19") (pin "1") (pinfunction "1_1") (pintype "passive"))
      (node (ref "R20") (pin "2") (pinfunction "2_2") (pintype "passive"))
    )
    (net (code "57") (name "Net-(R27A-CCW)") (class "Default")
      (node (ref "R27") (pin "1") (pinfunction "CCW_1") (pintype "passive"))
      (node (ref "R28") (pin "2") (pinfunction "2_2") (pintype "passive"))
    )
    (net (code "58") (name "Net-(R27A-W)") (class "Default")
      (node (ref "R23") (pin "2") (pinfunction "2_2") (pintype "passive"))
      (node (ref "R27") (pin "2") (pinfunction "W_2") (pintype "passive"))
    )
    (net (code "59") (name "Net-(R27B-CCW)") (class "Default")
      (node (ref "R27") (pin "1'") (pinfunction "CCW_1'") (pintype "passive"))
      (node (ref "R29") (pin "2") (pinfunction "2_2") (pintype "passive"))
    )
    (net (code "60") (name "Net-(R27B-W)") (class "Default")
      (node (ref "R26") (pin "2") (pinfunction "2_2") (pintype "passive"))
      (node (ref "R27") (pin "2'") (pinfunction "W_2'") (pintype "passive"))
    )
    (net (code "61") (name "Net-(SA1-CM)") (class "Default")
      (node (ref "R5") (pin "1") (pinfunction "1_1") (pintype "passive"))
      (node (ref "SA1") (pin "C") (pinfunction "CM_C") (pintype "passive"))
    )
    (net (code "62") (name "Net-(SA2A-CM)") (class "Default")
      (node (ref "R42") (pin "1") (pinfunction "1_1") (pintype "passive"))
      (node (ref "SA2") (pin "CMN") (pinfunction "CM_CMN") (pintype "passive"))
    )
    (net (code "63") (name "Net-(SA2B-CM)") (class "Default")
      (node (ref "R43") (pin "1") (pinfunction "1_1") (pintype "passive"))
      (node (ref "SA2") (pin "CMN'") (pinfunction "CM_CMN'") (pintype "passive"))
    )
    (net (code "64") (name "Net-(VT2-C)") (class "Default")
      (node (ref "R9") (pin "2") (pinfunction "2_2") (pintype "passive"))
      (node (ref "VT2") (pin "1") (pinfunction "C_1") (pintype "passive"))
    )
    (net (code "65") (name "Net-(VT3-B)") (class "Default")
      (node (ref "R12") (pin "2") (pinfunction "2_2") (pintype "passive"))
      (node (ref "R16") (pin "1") (pinfunction "1_1") (pintype "passive"))
      (node (ref "VT3") (pin "2") (pinfunction "B_2") (pintype "passive"))
    )
    (net (code "66") (name "unconnected-(DA6B-DIODE_BIAS-Pad2)") (class "Default")
      (node (ref "DA6") (pin "2") (pinfunction "DIODE_BIAS_2") (pintype "input"))
    )
    (net (code "67") (name "unconnected-(DA6C-DIODE_BIAS-Pad15)") (class "Default")
      (node (ref "DA6") (pin "15") (pinfunction "DIODE_BIAS_15") (pintype "input"))
    )
    (net (code "68") (name "unconnected-(DA7B-DIODE_BIAS-Pad2)") (class "Default")
      (node (ref "DA7") (pin "2") (pinfunction "DIODE_BIAS_2") (pintype "input"))
    )
    (net (code "69") (name "unconnected-(DA7C-DIODE_BIAS-Pad15)") (class "Default")
      (node (ref "DA7") (pin "15") (pinfunction "DIODE_BIAS_15") (pintype "input"))
    )
  )
)
